# TPSM84824MOL.net
KiCad netlist of a schematic drawn in Altium Designer
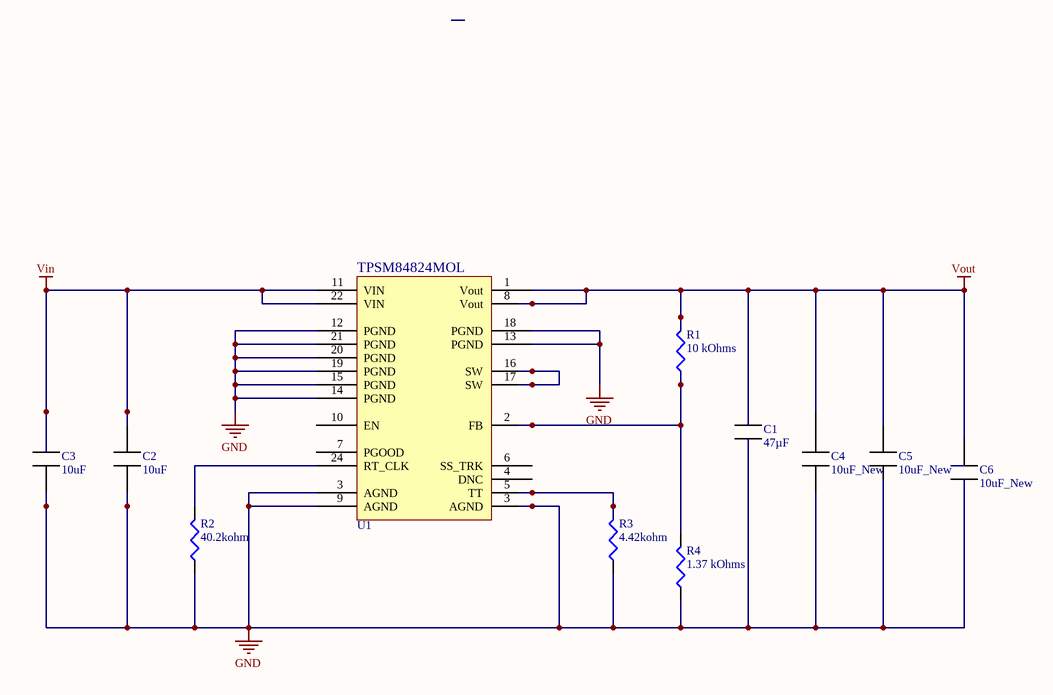
[diagram p0: TPSM84824MOL.SchDoc]

(export (version "E")
  (design (tool "Eeschema 10.0.6"))
  (components
    (comp (ref "C1")
      (value "47µF")
      (footprint "C/R0805")
      (description "47µF 6.3V Ceramic Capacitor X5R 0805 (2012 Metric) 0.079\" L x 0.049\" W (2.00mm x 1.25mm)")
      (fields
        (field (name "MANUFACTURER") "Murata")
        (field (name "MANUFACTURER PART NUMBER") "GRM21BR60J476ME15K")
      )
      (libsource (lib "TPSM84824MOL_PCB_Library") (part "GRM21BR60J476ME15K"))
    )
    (comp (ref "C2")
      (value "10uF")
      (footprint "C/R0805")
      (description "CAP CER 10UF 10V X5R 0805")
      (fields
        (field (name "MANUFACTURER") "KEMET")
        (field (name "MANUFACTURER PART NUMBER") "C0805C106K8PACTU")
      )
      (libsource (lib "TPSM84824MOL_PCB_Library") (part "C0805C106K8PACTU"))
    )
    (comp (ref "C3")
      (value "10uF")
      (footprint "C/R0805")
      (description "CAP CER 10UF 10V X5R 0805")
      (fields
        (field (name "MANUFACTURER") "KEMET")
        (field (name "MANUFACTURER PART NUMBER") "C0805C106K8PACTU")
      )
      (libsource (lib "TPSM84824MOL_PCB_Library") (part "C0805C106K8PACTU"))
    )
    (comp (ref "C4")
      (value "10uF_New")
      (footprint "CAPPM7343X310N")
      (description "CAP TANT 10UF 35V 20% 2917")
      (fields
        (field (name "MANUFACTURER") "KEMET")
        (field (name "MANUFACTURER PART NUMBER") "T495D106M035ATE125")
      )
      (libsource (lib "TPSM84824MOL_PCB_Library") (part "T495D106M035ATE125"))
    )
    (comp (ref "C5")
      (value "10uF_New")
      (footprint "CAPPM7343X310N")
      (description "CAP TANT 10UF 35V 20% 2917")
      (fields
        (field (name "MANUFACTURER") "KEMET")
        (field (name "MANUFACTURER PART NUMBER") "T495D106M035ATE125")
      )
      (libsource (lib "TPSM84824MOL_PCB_Library") (part "T495D106M035ATE125"))
    )
    (comp (ref "C6")
      (value "10uF_New")
      (footprint "CAPPM7343X310N")
      (description "CAP TANT 10UF 35V 20% 2917")
      (fields
        (field (name "MANUFACTURER") "KEMET")
        (field (name "MANUFACTURER PART NUMBER") "T495D106M035ATE125")
      )
      (libsource (lib "TPSM84824MOL_PCB_Library") (part "T495D106M035ATE125"))
    )
    (comp (ref "R1")
      (value "10 kOhms")
      (footprint "C/R0805")
      (description "RES SMD 10K OHM 1% 1/8W 0805")
      (fields
        (field (name "MANUFACTURER") "Yageo")
        (field (name "MANUFACTURER PART NUMBER") "RC0805FR-0710KL")
      )
      (libsource (lib "TPSM84824MOL_PCB_Library") (part "RC0805FR-0710KL"))
    )
    (comp (ref "R2")
      (value "40.2kohm")
      (footprint "C/R0805")
      (description "Res Thin Film 0805 40.2K Ohm 0.1% 1/8W 25ppm/C Molded SMD SMD Punched Carrier T/R")
      (fields
        (field (name "MANUFACTURER") "Panasonic")
        (field (name "MANUFACTURER PART NUMBER") "ERA-6AEB4022V")
      )
      (libsource (lib "TPSM84824MOL_PCB_Library") (part "ERA-6AEB4022V"))
    )
    (comp (ref "R3")
      (value "4.42kohm")
      (footprint "C/R0805")
      (description "Panasonic ERA Series Thin Film Surface Mount Fixed Resistor 0805 Case 4.42k 0.1% 0.125W 25ppm/C")
      (fields
        (field (name "MANUFACTURER") "Panasonic")
        (field (name "MANUFACTURER PART NUMBER") "ERA-6AEB4421V")
      )
      (libsource (lib "TPSM84824MOL_PCB_Library") (part "ERA-6AEB4421V"))
    )
    (comp (ref "R4")
      (value "1.37 kOhms")
      (footprint "C/R0805")
      (description "RES SMD 1.37K OHM 1% 1/16W 0402")
      (fields
        (field (name "MANUFACTURER") "Vishay")
        (field (name "MANUFACTURER PART NUMBER") "CRCW04021K37FKED")
      )
      (libsource (lib "TPSM84824MOL_PCB_Library") (part "RC0805FR-071K37L"))
    )
    (comp (ref "U1")
      (value "TPSM84824MOL")
      (footprint "TPSM84424MOLR")
      (description "DC DC CONVERTER 0.6-10V")
      (fields
        (field (name "MANUFACTURER") "Texas Instruments")
        (field (name "MANUFACTURER PART NUMBER") "TPSM84824MOLR")
      )
      (libsource (lib "TPSM84824MOL_PCB_Library") (part "TPSM84824MOL"))
    )
  )
  (nets
    (net (code "1") (name "GND") (class "Default")
      (node (ref "C1") (pin "3") (pintype "passive"))
      (node (ref "C2") (pin "1") (pinfunction "1_1") (pintype "passive"))
      (node (ref "C3") (pin "1") (pinfunction "1_1") (pintype "passive"))
      (node (ref "C6") (pin "3") (pintype "passive"))
      (node (ref "R2") (pin "1") (pinfunction "5_1") (pintype "passive"))
      (node (ref "R3") (pin "1") (pinfunction "5_1") (pintype "passive"))
      (node (ref "R4") (pin "1") (pinfunction "5_1") (pintype "passive"))
      (node (ref "U1") (pin "12") (pinfunction "PGND_12") (pintype "passive"))
      (node (ref "U1") (pin "13") (pinfunction "PGND_13") (pintype "passive"))
      (node (ref "U1") (pin "14") (pinfunction "PGND_14") (pintype "passive"))
      (node (ref "U1") (pin "15") (pinfunction "PGND_15") (pintype "passive"))
      (node (ref "U1") (pin "18") (pinfunction "PGND_18") (pintype "passive"))
      (node (ref "U1") (pin "19") (pinfunction "PGND_19") (pintype "passive"))
      (node (ref "U1") (pin "20") (pinfunction "PGND_20") (pintype "passive"))
      (node (ref "U1") (pin "21") (pinfunction "PGND_21") (pintype "passive"))
      (node (ref "U1") (pin "3") (pinfunction "AGND_3") (pintype "passive"))
      (node (ref "U1") (pin "9") (pinfunction "AGND_9") (pintype "passive"))
    )
    (net (code "2") (name "Net-(R1-5)") (class "Default")
      (node (ref "R1") (pin "1") (pinfunction "5_1") (pintype "passive"))
      (node (ref "R4") (pin "2") (pinfunction "6_2") (pintype "passive"))
      (node (ref "U1") (pin "2") (pinfunction "FB_2") (pintype "passive"))
    )
    (net (code "3") (name "Net-(R2-6)") (class "Default")
      (node (ref "R2") (pin "2") (pinfunction "6_2") (pintype "passive"))
      (node (ref "U1") (pin "24") (pinfunction "RT_CLK_24") (pintype "passive"))
    )
    (net (code "4") (name "Net-(R3-6)") (class "Default")
      (node (ref "R3") (pin "2") (pinfunction "6_2") (pintype "passive"))
      (node (ref "U1") (pin "5") (pinfunction "TT_5") (pintype "passive"))
    )
    (net (code "5") (name "Net-(U1-SW-Pad16)") (class "Default")
      (node (ref "U1") (pin "16") (pinfunction "SW_16") (pintype "passive"))
      (node (ref "U1") (pin "17") (pinfunction "SW_17") (pintype "passive"))
    )
    (net (code "6") (name "Vin") (class "Default")
      (node (ref "C2") (pin "2") (pinfunction "2_2") (pintype "passive"))
      (node (ref "C3") (pin "2") (pinfunction "2_2") (pintype "passive"))
      (node (ref "U1") (pin "11") (pinfunction "VIN_11") (pintype "passive"))
      (node (ref "U1") (pin "22") (pinfunction "VIN_22") (pintype "passive"))
    )
    (net (code "7") (name "Vout") (class "Default")
      (node (ref "C1") (pin "4") (pintype "passive"))
      (node (ref "R1") (pin "2") (pinfunction "6_2") (pintype "passive"))
      (node (ref "U1") (pin "1") (pinfunction "Vout_1") (pintype "passive"))
      (node (ref "U1") (pin "8") (pinfunction "Vout_8") (pintype "passive"))
    )
    (net (code "8") (name "unconnected-(C4-Pad3)") (class "Default")
      (node (ref "C4") (pin "3") (pintype "passive"))
    )
    (net (code "9") (name "unconnected-(C4-Pad4)") (class "Default")
      (node (ref "C4") (pin "4") (pintype "passive"))
    )
    (net (code "10") (name "unconnected-(C5-Pad3)") (class "Default")
      (node (ref "C5") (pin "3") (pintype "passive"))
    )
    (net (code "11") (name "unconnected-(C5-Pad4)") (class "Default")
      (node (ref "C5") (pin "4") (pintype "passive"))
    )
    (net (code "12") (name "unconnected-(C6-Pad4)") (class "Default")
      (node (ref "C6") (pin "4") (pintype "passive"))
    )
    (net (code "13") (name "unconnected-(U1-DNC-Pad4)") (class "Default")
      (node (ref "U1") (pin "4") (pinfunction "DNC_4") (pintype "passive"))
    )
    (net (code "14") (name "unconnected-(U1-EN-Pad10)") (class "Default")
      (node (ref "U1") (pin "10") (pinfunction "EN_10") (pintype "passive"))
    )
    (net (code "15") (name "unconnected-(U1-PGOOD-Pad7)") (class "Default")
      (node (ref "U1") (pin "7") (pinfunction "PGOOD_7") (pintype "passive"))
    )
    (net (code "16") (name "unconnected-(U1-SS_TRK-Pad6)") (class "Default")
      (node (ref "U1") (pin "6") (pinfunction "SS_TRK_6") (pintype "passive"))
    )
  )
)
